# esq.net
KiCad netlist of a schematic drawn in Altium Designer
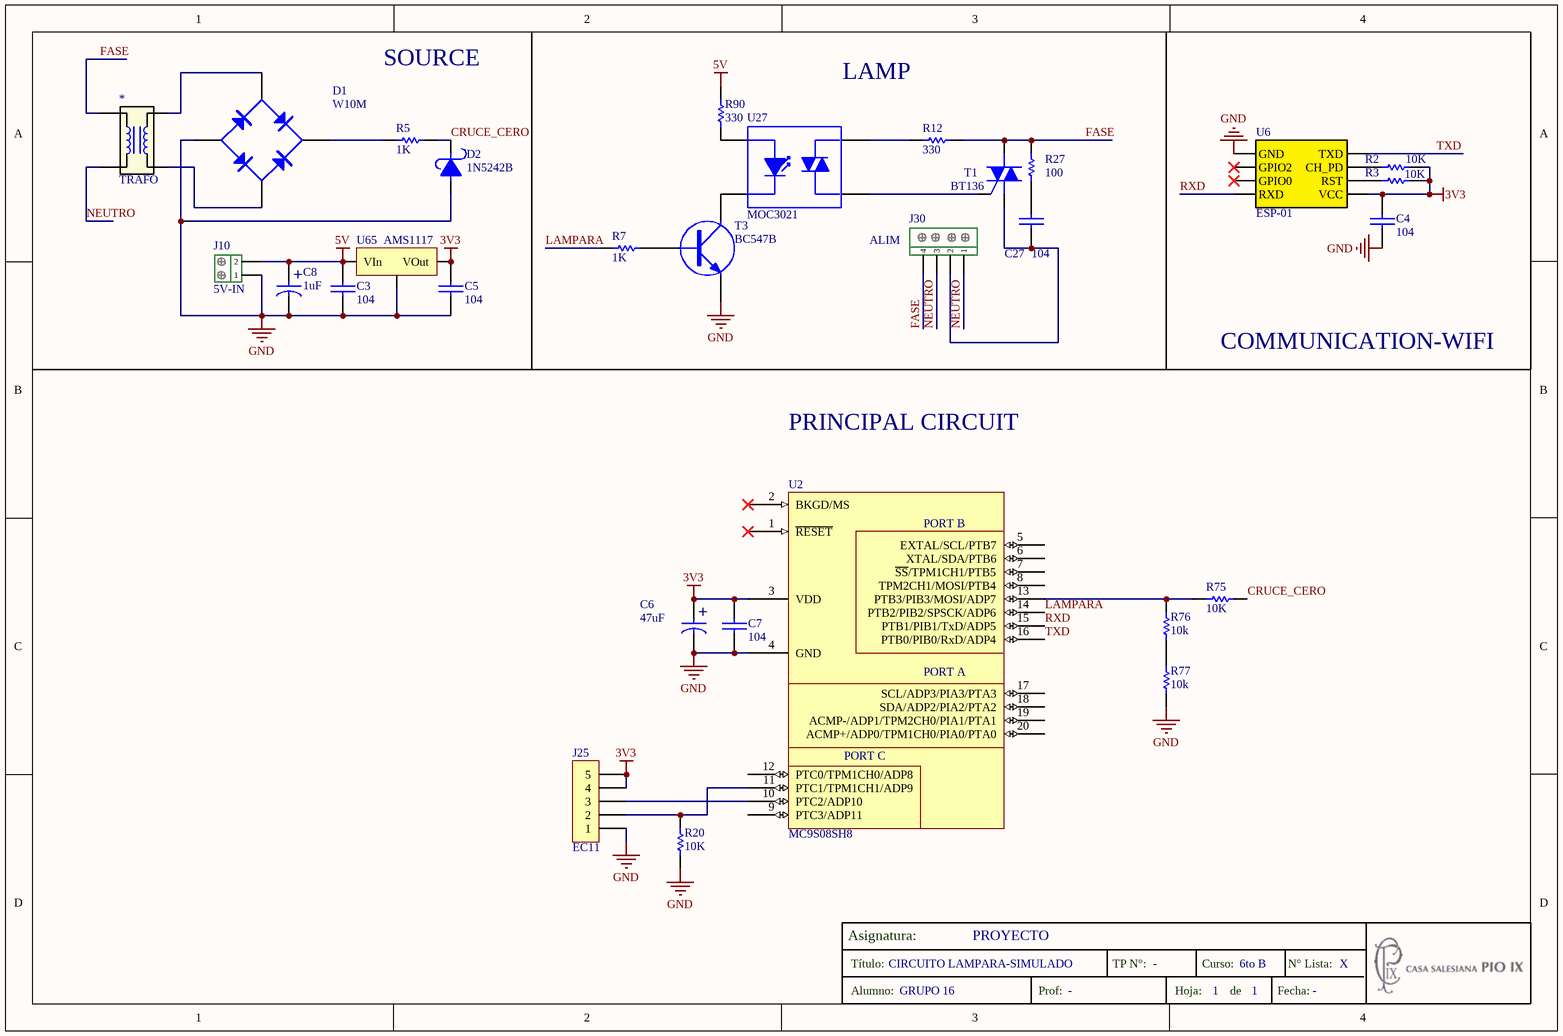
[diagram p0: esq.SchDoc]

(export (version "E")
  (design (tool "Eeschema 10.0.6"))
  (components
    (comp (ref "*") (value "TRAFO") (footprint "trafo chico") (libsource (lib "Schlib1") (part "TRAFO")))
    (comp (ref "C3")
      (value "104")
      (footprint "0805")
      (description "cap")
      (fields (field (name "AUTOR") "Guido Spataro"))
      (libsource (lib "Schlib1") (part "CAP"))
    )
    (comp (ref "C4")
      (value "104")
      (footprint "0805")
      (description "cap")
      (fields (field (name "AUTOR") "Guido Spataro"))
      (libsource (lib "scdlib") (part "CAP"))
    )
    (comp (ref "C5")
      (value "104")
      (footprint "0805")
      (description "cap")
      (fields (field (name "AUTOR") "Guido Spataro"))
      (libsource (lib "Schlib1") (part "CAP"))
    )
    (comp (ref "C6")
      (value "47uF")
      (footprint "CAP_SMD")
      (description "Cap polarizado")
      (libsource (lib "Schlib1") (part "CAPPOL"))
    )
    (comp (ref "C7")
      (value "104")
      (footprint "0805")
      (description "cap")
      (fields (field (name "AUTOR") "Guido Spataro"))
      (libsource (lib "Schlib1") (part "CAP"))
    )
    (comp (ref "C8")
      (value "1uF")
      (footprint "CAP_SMD")
      (description "Cap polarizado")
      (libsource (lib "Schlib1") (part "CAPPOL"))
    )
    (comp (ref "C27")
      (value "104")
      (footprint "0805")
      (description "cap")
      (fields (field (name "AUTOR") "Guido Spataro"))
      (libsource (lib "Schlib1") (part "CAP"))
    )
    (comp (ref "D1") (value "W10M") (footprint "PUENTE - W10M") (libsource (lib "Schlib1") (part "PUENTE")))
    (comp (ref "D2")
      (value "1N5242B")
      (footprint "Diodo")
      (description "Diodo")
      (fields (field (name "AUTOR") "Guido Spataro"))
      (libsource (lib "Schlib1") (part "DIODO SCHOTTKY"))
    )
    (comp (ref "J10")
      (value "5V-IN")
      (footprint "BORNERA2")
      (description "Bornera de 2 pines")
      (fields (field (name "AUTOR") "Guido Spataro"))
      (libsource (lib "Schlib1") (part "Bornera_2"))
    )
    (comp (ref "J25") (value "EC11") (footprint "BORNERA5") (libsource (lib "Schlib1") (part "BORNERA 5")))
    (comp (ref "J30") (value "ALIM") (footprint "BORNERA4") (libsource (lib "Schlib1") (part "BORNERA 4")))
    (comp (ref "R2")
      (value "10K")
      (footprint "0805")
      (description "Resistencia")
      (fields (field (name "AUTOR") "Guido Spataro"))
      (libsource (lib "scdlib") (part "RES"))
    )
    (comp (ref "R3")
      (value "10K")
      (footprint "0805")
      (description "Resistencia")
      (fields (field (name "AUTOR") "Guido Spataro"))
      (libsource (lib "scdlib") (part "RES"))
    )
    (comp (ref "R5")
      (value "1K")
      (footprint "0805")
      (description "Resistencia")
      (fields (field (name "AUTOR") "Guido Spataro"))
      (libsource (lib "Schlib1") (part "RES"))
    )
    (comp (ref "R7")
      (value "1K")
      (footprint "0805")
      (description "Resistencia")
      (fields (field (name "AUTOR") "Guido Spataro"))
      (libsource (lib "Schlib1") (part "RES"))
    )
    (comp (ref "R12")
      (value "330")
      (footprint "0805")
      (description "Resistencia")
      (fields (field (name "AUTOR") "Guido Spataro"))
      (libsource (lib "Schlib1") (part "RES"))
    )
    (comp (ref "R20")
      (value "10K")
      (footprint "0805")
      (description "Resistencia")
      (fields (field (name "AUTOR") "Guido Spataro"))
      (libsource (lib "Schlib1") (part "RES"))
    )
    (comp (ref "R27")
      (value "100")
      (footprint "0805")
      (description "Resistencia")
      (fields (field (name "AUTOR") "Guido Spataro"))
      (libsource (lib "Schlib1") (part "RES"))
    )
    (comp (ref "R75")
      (value "10K")
      (footprint "0805")
      (description "Resistencia")
      (fields (field (name "AUTOR") "Guido Spataro"))
      (libsource (lib "Schlib1") (part "RES"))
    )
    (comp (ref "R76")
      (value "10k")
      (footprint "0805")
      (description "Resistencia")
      (fields (field (name "AUTOR") "Guido Spataro"))
      (libsource (lib "Schlib1") (part "RES"))
    )
    (comp (ref "R77")
      (value "10k")
      (footprint "0805")
      (description "Resistencia")
      (fields (field (name "AUTOR") "Guido Spataro"))
      (libsource (lib "Schlib1") (part "RES"))
    )
    (comp (ref "R90")
      (value "330")
      (footprint "0805")
      (description "Resistencia")
      (fields (field (name "AUTOR") "Guido Spataro"))
      (libsource (lib "Schlib1") (part "RES"))
    )
    (comp (ref "T1") (value "BT136") (footprint "BT136") (libsource (lib "Schlib1") (part "BT136")))
    (comp (ref "T3") (value "BC547B") (footprint "SOT23") (libsource (lib "Schlib1") (part "TRANSISTOR NPN")))
    (comp (ref "U2")
      (value "MC9S08SH8")
      (footprint "SH8")
      (description "Micro controlador")
      (fields (field (name "AUTOR") "Guido Spataro"))
      (libsource (lib "Schlib1") (part "MC9S08SH8"))
    )
    (comp (ref "U6") (value "ESP-01") (footprint "ESP-01") (libsource (lib "Schlib1") (part "ESP-01")))
    (comp (ref "U27")
      (value "MOC3021")
      (footprint "MOC3021")
      (description "OPTO-ACOPLADOR")
      (libsource (lib "Schlib1") (part "MOC3021"))
    )
    (comp (ref "U65") (value "AMS1117") (footprint "AMS1117") (libsource (lib "Schlib1") (part "AMS1117")))
  )
  (nets
    (net (code "1") (name "/CRUCE_CERO") (class "Default")
      (node (ref "D2") (pin "2") (pinfunction "2_2") (pintype "passive"))
      (node (ref "R5") (pin "2") (pinfunction "2_2") (pintype "passive"))
      (node (ref "R75") (pin "1") (pinfunction "1_1") (pintype "passive"))
    )
    (net (code "2") (name "/FASE") (class "Default")
      (node (ref "*") (pin "1") (pinfunction "1_1") (pintype "passive"))
      (node (ref "J30") (pin "4") (pinfunction "4_4") (pintype "passive"))
      (node (ref "R12") (pin "1") (pinfunction "1_1") (pintype "passive"))
      (node (ref "R27") (pin "2") (pinfunction "2_2") (pintype "passive"))
      (node (ref "T1") (pin "2") (pinfunction "M2_2") (pintype "passive"))
    )
    (net (code "3") (name "/LAMPARA") (class "Default")
      (node (ref "R7") (pin "2") (pinfunction "2_2") (pintype "passive"))
      (node (ref "U2") (pin "14") (pinfunction "PTB2/PIB2/SPSCK/ADP6_14") (pintype "bidirectional"))
    )
    (net (code "4") (name "/NEUTRO") (class "Default")
      (node (ref "*") (pin "5") (pinfunction "5_5") (pintype "passive"))
      (node (ref "J30") (pin "1") (pinfunction "1_1") (pintype "passive"))
      (node (ref "J30") (pin "3") (pinfunction "3_3") (pintype "passive"))
    )
    (net (code "5") (name "/RXD") (class "Default")
      (node (ref "U2") (pin "15") (pinfunction "PTB1/PIB1/TxD/ADP5_15") (pintype "bidirectional"))
      (node (ref "U6") (pin "4") (pinfunction "RXD_4") (pintype "passive"))
    )
    (net (code "6") (name "/TXD") (class "Default")
      (node (ref "U2") (pin "16") (pinfunction "PTB0/PIB0/RxD/ADP4_16") (pintype "bidirectional"))
      (node (ref "U6") (pin "5") (pinfunction "TXD_5") (pintype "passive"))
    )
    (net (code "7") (name "3V3") (class "Default")
      (node (ref "C4") (pin "2") (pinfunction "2_2") (pintype "passive"))
      (node (ref "C5") (pin "1") (pinfunction "1_1") (pintype "passive"))
      (node (ref "C6") (pin "1") (pinfunction "1_1") (pintype "passive"))
      (node (ref "C7") (pin "1") (pinfunction "1_1") (pintype "passive"))
      (node (ref "J25") (pin "4") (pinfunction "4_4") (pintype "passive"))
      (node (ref "J25") (pin "5") (pinfunction "5_5") (pintype "passive"))
      (node (ref "R2") (pin "1") (pinfunction "1_1") (pintype "passive"))
      (node (ref "R3") (pin "1") (pinfunction "1_1") (pintype "passive"))
      (node (ref "U2") (pin "3") (pinfunction "VDD_3") (pintype "passive"))
      (node (ref "U6") (pin "8") (pinfunction "VCC_8") (pintype "passive"))
      (node (ref "U65") (pin "3") (pinfunction "VOut_3") (pintype "passive"))
    )
    (net (code "8") (name "5V") (class "Default")
      (node (ref "C3") (pin "1") (pinfunction "1_1") (pintype "passive"))
      (node (ref "C8") (pin "1") (pinfunction "1_1") (pintype "passive"))
      (node (ref "J10") (pin "2") (pinfunction "2_2") (pintype "passive"))
      (node (ref "R90") (pin "1") (pinfunction "1_1") (pintype "passive"))
      (node (ref "U65") (pin "1") (pinfunction "VIn_1") (pintype "passive"))
    )
    (net (code "9") (name "GND") (class "Default")
      (node (ref "C3") (pin "2") (pinfunction "2_2") (pintype "passive"))
      (node (ref "C4") (pin "1") (pinfunction "1_1") (pintype "passive"))
      (node (ref "C5") (pin "2") (pinfunction "2_2") (pintype "passive"))
      (node (ref "C6") (pin "2") (pinfunction "2_2") (pintype "passive"))
      (node (ref "C7") (pin "2") (pinfunction "2_2") (pintype "passive"))
      (node (ref "C8") (pin "2") (pinfunction "2_2") (pintype "passive"))
      (node (ref "D1") (pin "3") (pinfunction "V-_3") (pintype "passive"))
      (node (ref "D2") (pin "1") (pinfunction "1_1") (pintype "passive"))
      (node (ref "J10") (pin "1") (pinfunction "1_1") (pintype "passive"))
      (node (ref "J25") (pin "1") (pinfunction "1_1") (pintype "passive"))
      (node (ref "R20") (pin "1") (pinfunction "1_1") (pintype "passive"))
      (node (ref "R77") (pin "1") (pinfunction "1_1") (pintype "passive"))
      (node (ref "T3") (pin "3") (pinfunction "E_3") (pintype "passive"))
      (node (ref "U2") (pin "4") (pinfunction "GND_4") (pintype "passive"))
      (node (ref "U6") (pin "1") (pinfunction "GND_1") (pintype "passive"))
      (node (ref "U65") (pin "2") (pinfunction "GND_2") (pintype "passive"))
    )
    (net (code "10") (name "Net-(*-Pad7)") (class "Default")
      (node (ref "*") (pin "7") (pinfunction "7_7") (pintype "passive"))
      (node (ref "D1") (pin "2") (pinfunction "AC_2") (pintype "passive"))
    )
    (net (code "11") (name "Net-(*-Pad9)") (class "Default")
      (node (ref "*") (pin "9") (pinfunction "9_9") (pintype "passive"))
      (node (ref "D1") (pin "4") (pinfunction "AC_4") (pintype "passive"))
    )
    (net (code "12") (name "Net-(C27-Pad1)") (class "Default")
      (node (ref "C27") (pin "1") (pinfunction "1_1") (pintype "passive"))
      (node (ref "R27") (pin "1") (pinfunction "1_1") (pintype "passive"))
    )
    (net (code "13") (name "Net-(D1-V+)") (class "Default")
      (node (ref "D1") (pin "1") (pinfunction "V+_1") (pintype "passive"))
      (node (ref "R5") (pin "1") (pinfunction "1_1") (pintype "passive"))
    )
    (net (code "14") (name "Net-(R76-Pad1)") (class "Default")
      (node (ref "R76") (pin "1") (pinfunction "1_1") (pintype "passive"))
      (node (ref "R77") (pin "2") (pinfunction "2_2") (pintype "passive"))
    )
    (net (code "15") (name "Net-(T1-G)") (class "Default")
      (node (ref "T1") (pin "3") (pinfunction "G_3") (pintype "passive"))
      (node (ref "U27") (pin "4") (pinfunction "E_4") (pintype "passive"))
    )
    (net (code "16") (name "Net-(T1-M1)") (class "Default")
      (node (ref "C27") (pin "2") (pinfunction "2_2") (pintype "passive"))
      (node (ref "J30") (pin "2") (pinfunction "2_2") (pintype "passive"))
      (node (ref "T1") (pin "1") (pinfunction "M1_1") (pintype "passive"))
    )
    (net (code "17") (name "Net-(T3-B)") (class "Default")
      (node (ref "R7") (pin "1") (pinfunction "1_1") (pintype "passive"))
      (node (ref "T3") (pin "1") (pinfunction "B_1") (pintype "passive"))
    )
    (net (code "18") (name "Net-(T3-C)") (class "Default")
      (node (ref "T3") (pin "2") (pinfunction "C_2") (pintype "passive"))
      (node (ref "U27") (pin "2") (pinfunction "K_2") (pintype "passive"))
    )
    (net (code "19") (name "Net-(U2-PTB3{slash}PIB3{slash}MOSI{slash}ADP7)") (class "Default")
      (node (ref "R75") (pin "2") (pinfunction "2_2") (pintype "passive"))
      (node (ref "R76") (pin "2") (pinfunction "2_2") (pintype "passive"))
      (node (ref "U2") (pin "13") (pinfunction "PTB3/PIB3/MOSI/ADP7_13") (pintype "bidirectional"))
    )
    (net (code "20") (name "Net-(U2-PTC1{slash}TPM1CH1{slash}ADP9)") (class "Default")
      (node (ref "J25") (pin "2") (pinfunction "2_2") (pintype "passive"))
      (node (ref "R20") (pin "2") (pinfunction "2_2") (pintype "passive"))
      (node (ref "U2") (pin "11") (pinfunction "PTC1/TPM1CH1/ADP9_11") (pintype "bidirectional"))
    )
    (net (code "21") (name "Net-(U2-PTC2{slash}ADP10)") (class "Default")
      (node (ref "J25") (pin "3") (pinfunction "3_3") (pintype "passive"))
      (node (ref "U2") (pin "10") (pinfunction "PTC2/ADP10_10") (pintype "bidirectional"))
    )
    (net (code "22") (name "Net-(U6-CH_PD)") (class "Default")
      (node (ref "R2") (pin "2") (pinfunction "2_2") (pintype "passive"))
      (node (ref "U6") (pin "6") (pinfunction "CH_PD_6") (pintype "passive"))
    )
    (net (code "23") (name "Net-(U6-RST)") (class "Default")
      (node (ref "R3") (pin "2") (pinfunction "2_2") (pintype "passive"))
      (node (ref "U6") (pin "7") (pinfunction "RST_7") (pintype "passive"))
    )
    (net (code "24") (name "Net-(U27-A)") (class "Default")
      (node (ref "R90") (pin "2") (pinfunction "2_2") (pintype "passive"))
      (node (ref "U27") (pin "1") (pinfunction "A_1") (pintype "passive"))
    )
    (net (code "25") (name "Net-(U27-C)") (class "Default")
      (node (ref "R12") (pin "2") (pinfunction "2_2") (pintype "passive"))
      (node (ref "U27") (pin "6") (pinfunction "C_6") (pintype "passive"))
    )
    (net (code "26") (name "unconnected-(U2-ACMP+{slash}ADP0{slash}TPM1CH0{slash}PIA0{slash}PTA0-Pad20)") (class "Default")
      (node (ref "U2") (pin "20") (pinfunction "ACMP+/ADP0/TPM1CH0/PIA0/PTA0_20") (pintype "bidirectional"))
    )
    (net (code "27") (name "unconnected-(U2-ACMP-{slash}ADP1{slash}TPM2CH0{slash}PIA1{slash}PTA1-Pad19)") (class "Default")
      (node (ref "U2") (pin "19") (pinfunction "ACMP-/ADP1/TPM2CH0/PIA1/PTA1_19") (pintype "bidirectional"))
    )
    (net (code "28") (name "unconnected-(U2-BKGD{slash}MS-Pad2)") (class "Default")
      (node (ref "U2") (pin "2") (pinfunction "BKGD/MS_2") (pintype "input+no_connect"))
    )
    (net (code "29") (name "unconnected-(U2-EXTAL{slash}SCL{slash}PTB7-Pad5)") (class "Default")
      (node (ref "U2") (pin "5") (pinfunction "EXTAL/SCL/PTB7_5") (pintype "bidirectional"))
    )
    (net (code "30") (name "unconnected-(U2-PTC0{slash}TPM1CH0{slash}ADP8-Pad12)") (class "Default")
      (node (ref "U2") (pin "12") (pinfunction "PTC0/TPM1CH0/ADP8_12") (pintype "bidirectional"))
    )
    (net (code "31") (name "unconnected-(U2-PTC3{slash}ADP11-Pad9)") (class "Default")
      (node (ref "U2") (pin "9") (pinfunction "PTC3/ADP11_9") (pintype "bidirectional"))
    )
    (net (code "32") (name "unconnected-(U2-SCL{slash}ADP3{slash}PIA3{slash}PTA3-Pad17)") (class "Default")
      (node (ref "U2") (pin "17") (pinfunction "SCL/ADP3/PIA3/PTA3_17") (pintype "bidirectional"))
    )
    (net (code "33") (name "unconnected-(U2-SDA{slash}ADP2{slash}PIA2{slash}PTA2-Pad18)") (class "Default")
      (node (ref "U2") (pin "18") (pinfunction "SDA/ADP2/PIA2/PTA2_18") (pintype "bidirectional"))
    )
    (net (code "34") (name "unconnected-(U2-TPM2CH1{slash}MOSI{slash}PTB4-Pad8)") (class "Default")
      (node (ref "U2") (pin "8") (pinfunction "TPM2CH1/MOSI/PTB4_8") (pintype "bidirectional"))
    )
    (net (code "35") (name "unconnected-(U2-XTAL{slash}SDA{slash}PTB6-Pad6)") (class "Default")
      (node (ref "U2") (pin "6") (pinfunction "XTAL/SDA/PTB6_6") (pintype "bidirectional"))
    )
    (net (code "36") (name "unconnected-(U2-~{RESET}-Pad1)") (class "Default")
      (node (ref "U2") (pin "1") (pinfunction "~{RESET}_1") (pintype "input+no_connect"))
    )
    (net (code "37") (name "unconnected-(U2-~{SS}{slash}TPM1CH1{slash}PTB5-Pad7)") (class "Default")
      (node (ref "U2") (pin "7") (pinfunction "~{SS}/TPM1CH1/PTB5_7") (pintype "bidirectional"))
    )
    (net (code "38") (name "unconnected-(U6-GPIO0-Pad3)") (class "Default")
      (node (ref "U6") (pin "3") (pinfunction "GPIO0_3") (pintype "passive+no_connect"))
    )
    (net (code "39") (name "unconnected-(U6-GPIO2-Pad2)") (class "Default")
      (node (ref "U6") (pin "2") (pinfunction "GPIO2_2") (pintype "passive+no_connect"))
    )
  )
)
